# IO_Filter.net
KiCad netlist of a schematic drawn in Altium Designer
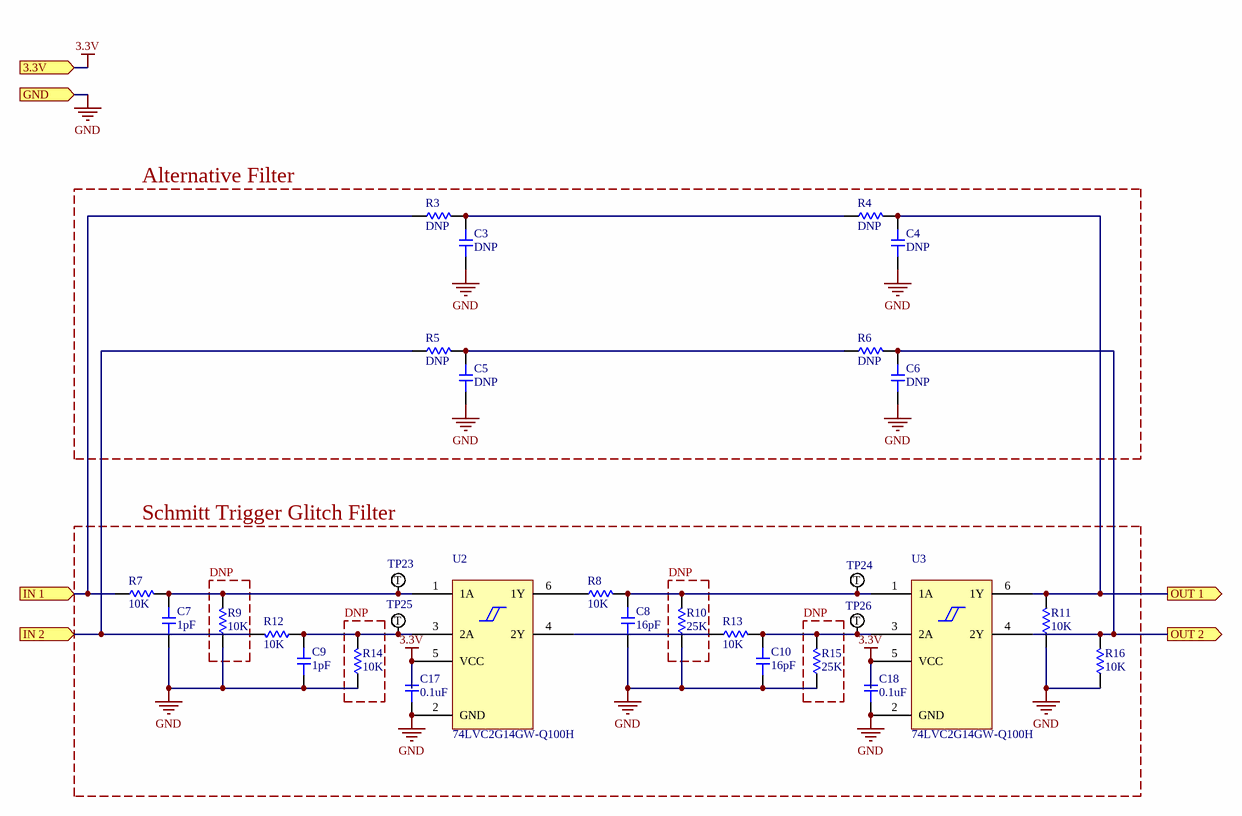
[diagram p0: IO_Filter.SchDoc]

(export (version "E")
  (design (tool "Eeschema 10.0.6"))
  (components
    (comp (ref "C3") (value "DNP") (footprint "0603-CAP") (libsource (lib "IO_Converter") (part "Capacitor")))
    (comp (ref "C4") (value "DNP") (footprint "0603-CAP") (libsource (lib "IO_Converter") (part "Capacitor")))
    (comp (ref "C5") (value "DNP") (footprint "0603-CAP") (libsource (lib "IO_Converter") (part "Capacitor")))
    (comp (ref "C6") (value "DNP") (footprint "0603-CAP") (libsource (lib "IO_Converter") (part "Capacitor")))
    (comp (ref "C7")
      (value "1pF")
      (footprint "0603-CAP")
      (description "±0.1pF 50V Ceramic Capacitor C0G, NP0 0603 (1608 Metric)")
      (fields (field (name "Comment") "CC0603BRNPO9BN1R0"))
      (libsource (lib "IO_Converter") (part "Capacitor 1pF"))
    )
    (comp (ref "C8")
      (value "16pF")
      (footprint "0603-CAP")
      (description "±5% 50V Ceramic Capacitor C0G, NP0 0603 (1608 Metric)")
      (fields (field (name "Comment") "CC0603JRNPO9BN160"))
      (libsource (lib "IO_Converter") (part "Capacitor 16pF"))
    )
    (comp (ref "C9")
      (value "1pF")
      (footprint "0603-CAP")
      (description "±0.1pF 50V Ceramic Capacitor C0G, NP0 0603 (1608 Metric)")
      (fields (field (name "Comment") "CC0603BRNPO9BN1R0"))
      (libsource (lib "IO_Converter") (part "Capacitor 1pF"))
    )
    (comp (ref "C10")
      (value "16pF")
      (footprint "0603-CAP")
      (description "±5% 50V Ceramic Capacitor C0G, NP0 0603 (1608 Metric)")
      (fields (field (name "Comment") "CC0603JRNPO9BN160"))
      (libsource (lib "IO_Converter") (part "Capacitor 16pF"))
    )
    (comp (ref "C17")
      (value "0.1uF")
      (footprint "0603-CAP")
      (description "0.1µF ±10% 25V Ceramic Capacitor X7R 0603 (1608 Metric)")
      (fields (field (name "Comment") "CC0603KRX7R8BB104"))
      (libsource (lib "IO_Converter") (part "Capacitor 0.1uF"))
    )
    (comp (ref "C18")
      (value "0.1uF")
      (footprint "0603-CAP")
      (description "0.1µF ±10% 25V Ceramic Capacitor X7R 0603 (1608 Metric)")
      (fields (field (name "Comment") "CC0603KRX7R8BB104"))
      (libsource (lib "IO_Converter") (part "Capacitor 0.1uF"))
    )
    (comp (ref "R3") (value "DNP") (footprint "0603-RES") (libsource (lib "IO_Converter") (part "Resistor")))
    (comp (ref "R4") (value "DNP") (footprint "0603-RES") (libsource (lib "IO_Converter") (part "Resistor")))
    (comp (ref "R5") (value "DNP") (footprint "0603-RES") (libsource (lib "IO_Converter") (part "Resistor")))
    (comp (ref "R6") (value "DNP") (footprint "0603-RES") (libsource (lib "IO_Converter") (part "Resistor")))
    (comp (ref "R7")
      (value "10K")
      (footprint "0603-RES")
      (description "10 ±0.5% 0.1W, 1/10W Chip Resistor 0603 (1608 Metric) - Thin Film")
      (fields (field (name "Comment") "RT0603DRE0710KL"))
      (libsource (lib "IO_Converter") (part "Resisitor 10K"))
    )
    (comp (ref "R8")
      (value "10K")
      (footprint "0603-RES")
      (description "10 ±0.5% 0.1W, 1/10W Chip Resistor 0603 (1608 Metric) - Thin Film")
      (fields (field (name "Comment") "RT0603DRE0710KL"))
      (libsource (lib "IO_Converter") (part "Resisitor 10K"))
    )
    (comp (ref "R9")
      (value "10K")
      (footprint "0603-RES")
      (description "10 ±0.5% 0.1W, 1/10W Chip Resistor 0603 (1608 Metric) - Thin Film")
      (fields (field (name "Comment") "RT0603DRE0710KL"))
      (libsource (lib "IO_Converter") (part "Resisitor 10K"))
    )
    (comp (ref "R10")
      (value "25K")
      (footprint "RESC2012X06N")
      (fields (field (name "Comment") "CPF-A-0805B25KE"))
      (libsource (lib "IO_Converter") (part "Resistor 25K"))
    )
    (comp (ref "R11")
      (value "10K")
      (footprint "0603-RES")
      (description "10 ±0.5% 0.1W, 1/10W Chip Resistor 0603 (1608 Metric) - Thin Film")
      (fields (field (name "Comment") "RT0603DRE0710KL"))
      (libsource (lib "IO_Converter") (part "Resisitor 10K"))
    )
    (comp (ref "R12")
      (value "10K")
      (footprint "0603-RES")
      (description "10 ±0.5% 0.1W, 1/10W Chip Resistor 0603 (1608 Metric) - Thin Film")
      (fields (field (name "Comment") "RT0603DRE0710KL"))
      (libsource (lib "IO_Converter") (part "Resisitor 10K"))
    )
    (comp (ref "R13")
      (value "10K")
      (footprint "0603-RES")
      (description "10 ±0.5% 0.1W, 1/10W Chip Resistor 0603 (1608 Metric) - Thin Film")
      (fields (field (name "Comment") "RT0603DRE0710KL"))
      (libsource (lib "IO_Converter") (part "Resisitor 10K"))
    )
    (comp (ref "R14")
      (value "10K")
      (footprint "0603-RES")
      (description "10 ±0.5% 0.1W, 1/10W Chip Resistor 0603 (1608 Metric) - Thin Film")
      (fields (field (name "Comment") "RT0603DRE0710KL"))
      (libsource (lib "IO_Converter") (part "Resisitor 10K"))
    )
    (comp (ref "R15")
      (value "25K")
      (footprint "RESC2012X06N")
      (fields (field (name "Comment") "CPF-A-0805B25KE"))
      (libsource (lib "IO_Converter") (part "Resistor 25K"))
    )
    (comp (ref "R16")
      (value "10K")
      (footprint "0603-RES")
      (description "10 ±0.5% 0.1W, 1/10W Chip Resistor 0603 (1608 Metric) - Thin Film")
      (fields (field (name "Comment") "RT0603DRE0710KL"))
      (libsource (lib "IO_Converter") (part "Resisitor 10K"))
    )
    (comp (ref "TP23")
      (value "RCU-0C")
      (footprint "RCU-0C")
      (description "PC TEST POINT NATURAL")
      (libsource (lib "IO_Converter") (part "Test Point"))
    )
    (comp (ref "TP24")
      (value "RCU-0C")
      (footprint "RCU-0C")
      (description "PC TEST POINT NATURAL")
      (libsource (lib "IO_Converter") (part "Test Point"))
    )
    (comp (ref "TP25")
      (value "RCU-0C")
      (footprint "RCU-0C")
      (description "PC TEST POINT NATURAL")
      (libsource (lib "IO_Converter") (part "Test Point"))
    )
    (comp (ref "TP26")
      (value "RCU-0C")
      (footprint "RCU-0C")
      (description "PC TEST POINT NATURAL")
      (libsource (lib "IO_Converter") (part "Test Point"))
    )
    (comp (ref "U2")
      (value "74LVC2G14GW-Q100H")
      (footprint "TSOP65P210X110-6N")
      (description "Inverter IC 2 Channel Schmitt Trigger SOT-363")
      (libsource (lib "IO_Converter") (part "74LVC2G14GW-Q100H"))
    )
    (comp (ref "U3")
      (value "74LVC2G14GW-Q100H")
      (footprint "TSOP65P210X110-6N")
      (description "Inverter IC 2 Channel Schmitt Trigger SOT-363")
      (libsource (lib "IO_Converter") (part "74LVC2G14GW-Q100H"))
    )
  )
  (nets
    (net (code "1") (name "/IN 1") (class "Default")
      (node (ref "R3") (pin "1") (pinfunction "1_1") (pintype "passive"))
      (node (ref "R7") (pin "1") (pinfunction "1_1") (pintype "passive"))
    )
    (net (code "2") (name "/IN 2") (class "Default")
      (node (ref "R12") (pin "2") (pinfunction "2_2") (pintype "passive"))
      (node (ref "R5") (pin "1") (pinfunction "1_1") (pintype "passive"))
    )
    (net (code "3") (name "/OUT 1") (class "Default")
      (node (ref "C4") (pin "2") (pinfunction "2_2") (pintype "passive"))
      (node (ref "R11") (pin "2") (pinfunction "2_2") (pintype "passive"))
      (node (ref "R4") (pin "2") (pinfunction "2_2") (pintype "passive"))
      (node (ref "U3") (pin "6") (pinfunction "1Y_6") (pintype "passive"))
    )
    (net (code "4") (name "/OUT 2") (class "Default")
      (node (ref "C6") (pin "2") (pinfunction "2_2") (pintype "passive"))
      (node (ref "R16") (pin "2") (pinfunction "2_2") (pintype "passive"))
      (node (ref "R6") (pin "2") (pinfunction "2_2") (pintype "passive"))
      (node (ref "U3") (pin "4") (pinfunction "2Y_4") (pintype "passive"))
    )
    (net (code "5") (name "3.3V") (class "Default")
      (node (ref "C17") (pin "2") (pinfunction "2_2") (pintype "passive"))
      (node (ref "C18") (pin "2") (pinfunction "2_2") (pintype "passive"))
      (node (ref "U2") (pin "5") (pinfunction "VCC_5") (pintype "passive"))
      (node (ref "U3") (pin "5") (pinfunction "VCC_5") (pintype "passive"))
    )
    (net (code "6") (name "GND") (class "Default")
      (node (ref "C10") (pin "1") (pinfunction "1_1") (pintype "passive"))
      (node (ref "C17") (pin "1") (pinfunction "1_1") (pintype "passive"))
      (node (ref "C18") (pin "1") (pinfunction "1_1") (pintype "passive"))
      (node (ref "C3") (pin "1") (pinfunction "1_1") (pintype "passive"))
      (node (ref "C4") (pin "1") (pinfunction "1_1") (pintype "passive"))
      (node (ref "C5") (pin "1") (pinfunction "1_1") (pintype "passive"))
      (node (ref "C6") (pin "1") (pinfunction "1_1") (pintype "passive"))
      (node (ref "C7") (pin "1") (pinfunction "1_1") (pintype "passive"))
      (node (ref "C8") (pin "1") (pinfunction "1_1") (pintype "passive"))
      (node (ref "C9") (pin "1") (pinfunction "1_1") (pintype "passive"))
      (node (ref "R10") (pin "1") (pinfunction "1_1") (pintype "passive"))
      (node (ref "R11") (pin "1") (pinfunction "1_1") (pintype "passive"))
      (node (ref "R14") (pin "1") (pinfunction "1_1") (pintype "passive"))
      (node (ref "R15") (pin "1") (pinfunction "1_1") (pintype "passive"))
      (node (ref "R16") (pin "1") (pinfunction "1_1") (pintype "passive"))
      (node (ref "R9") (pin "1") (pinfunction "1_1") (pintype "passive"))
      (node (ref "U2") (pin "2") (pinfunction "GND_2") (pintype "passive"))
      (node (ref "U3") (pin "2") (pinfunction "GND_2") (pintype "passive"))
    )
    (net (code "7") (name "Net-(C3-Pad2)") (class "Default")
      (node (ref "C3") (pin "2") (pinfunction "2_2") (pintype "passive"))
      (node (ref "R3") (pin "2") (pinfunction "2_2") (pintype "passive"))
      (node (ref "R4") (pin "1") (pinfunction "1_1") (pintype "passive"))
    )
    (net (code "8") (name "Net-(C5-Pad2)") (class "Default")
      (node (ref "C5") (pin "2") (pinfunction "2_2") (pintype "passive"))
      (node (ref "R5") (pin "2") (pinfunction "2_2") (pintype "passive"))
      (node (ref "R6") (pin "1") (pinfunction "1_1") (pintype "passive"))
    )
    (net (code "9") (name "Net-(U2-1A)") (class "Default")
      (node (ref "C7") (pin "2") (pinfunction "2_2") (pintype "passive"))
      (node (ref "R7") (pin "2") (pinfunction "2_2") (pintype "passive"))
      (node (ref "R9") (pin "2") (pinfunction "2_2") (pintype "passive"))
      (node (ref "TP23") (pin "1") (pinfunction "1_1") (pintype "passive"))
      (node (ref "U2") (pin "1") (pinfunction "1A_1") (pintype "passive"))
    )
    (net (code "10") (name "Net-(U2-1Y)") (class "Default")
      (node (ref "R8") (pin "1") (pinfunction "1_1") (pintype "passive"))
      (node (ref "U2") (pin "6") (pinfunction "1Y_6") (pintype "passive"))
    )
    (net (code "11") (name "Net-(U2-2A)") (class "Default")
      (node (ref "C9") (pin "2") (pinfunction "2_2") (pintype "passive"))
      (node (ref "R12") (pin "1") (pinfunction "1_1") (pintype "passive"))
      (node (ref "R14") (pin "2") (pinfunction "2_2") (pintype "passive"))
      (node (ref "TP25") (pin "1") (pinfunction "1_1") (pintype "passive"))
      (node (ref "U2") (pin "3") (pinfunction "2A_3") (pintype "passive"))
    )
    (net (code "12") (name "Net-(U2-2Y)") (class "Default")
      (node (ref "R13") (pin "1") (pinfunction "1_1") (pintype "passive"))
      (node (ref "U2") (pin "4") (pinfunction "2Y_4") (pintype "passive"))
    )
    (net (code "13") (name "Net-(U3-1A)") (class "Default")
      (node (ref "C8") (pin "2") (pinfunction "2_2") (pintype "passive"))
      (node (ref "R10") (pin "2") (pinfunction "2_2") (pintype "passive"))
      (node (ref "R8") (pin "2") (pinfunction "2_2") (pintype "passive"))
      (node (ref "TP24") (pin "1") (pinfunction "1_1") (pintype "passive"))
      (node (ref "U3") (pin "1") (pinfunction "1A_1") (pintype "passive"))
    )
    (net (code "14") (name "Net-(U3-2A)") (class "Default")
      (node (ref "C10") (pin "2") (pinfunction "2_2") (pintype "passive"))
      (node (ref "R13") (pin "2") (pinfunction "2_2") (pintype "passive"))
      (node (ref "R15") (pin "2") (pinfunction "2_2") (pintype "passive"))
      (node (ref "TP26") (pin "1") (pinfunction "1_1") (pintype "passive"))
      (node (ref "U3") (pin "3") (pinfunction "2A_3") (pintype "passive"))
    )
  )
)
